# esp32md1.net
KiCad netlist of a schematic drawn in EAGLE
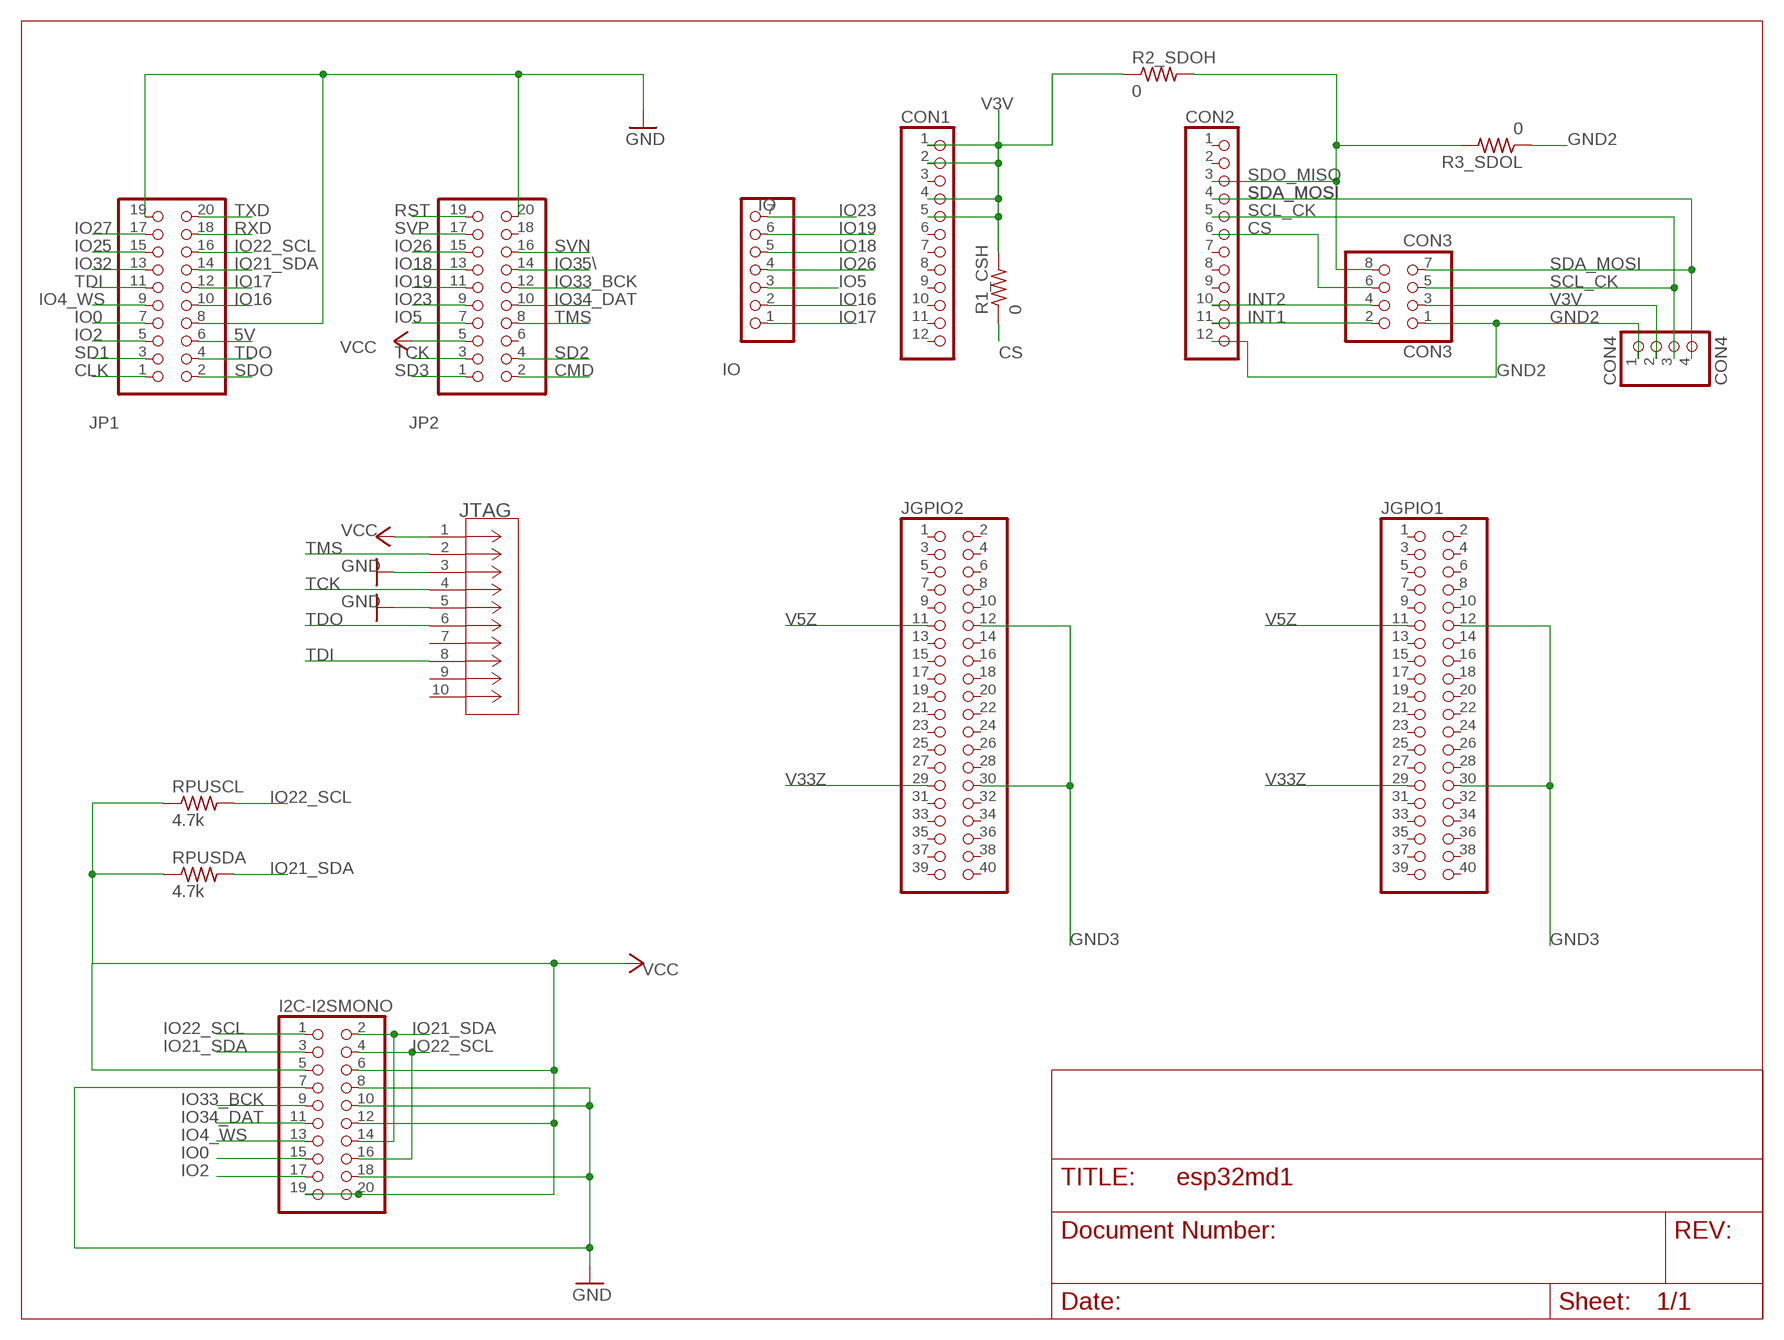
[diagram p0: schematic, sheet 1]

(export (version "E")
  (design (tool "Eeschema 10.0.6"))
  (components
    (comp (ref "CON1")
      (value "PINHD-1X12")
      (footprint "eagle-import:1X12")
      (libsource (lib "eagle-import") (part "PINHD-1X12"))
    )
    (comp (ref "CON2")
      (value "PINHD-1X12")
      (footprint "eagle-import:1X12")
      (libsource (lib "eagle-import") (part "PINHD-1X12"))
    )
    (comp (ref "CON3")
      (value "CON3")
      (footprint "eagle-import:2X04")
      (libsource (lib "eagle-import") (part "PINHD-2X4"))
    )
    (comp (ref "CON4")
      (value "CON4")
      (footprint "eagle-import:1X04")
      (libsource (lib "eagle-import") (part "PINHD-1X4"))
    )
    (comp (ref "I2C-I2SMONO")
      (value "PINHD-2X10")
      (footprint "eagle-import:2X10")
      (libsource (lib "eagle-import") (part "PINHD-2X10"))
    )
    (comp (ref "IO")
      (value "IO")
      (footprint "eagle-import:1X07")
      (libsource (lib "eagle-import") (part "PINHD-1X7"))
    )
    (comp (ref "JGPIO1")
      (value "PINHD-2X20")
      (footprint "eagle-import:2X20")
      (libsource (lib "eagle-import") (part "PINHD-2X20"))
    )
    (comp (ref "JGPIO2")
      (value "PINHD-2X20")
      (footprint "eagle-import:2X20")
      (libsource (lib "eagle-import") (part "PINHD-2X20"))
    )
    (comp (ref "JP1")
      (value "PINHD-2X10")
      (footprint "eagle-import:2X10")
      (libsource (lib "eagle-import") (part "PINHD-2X10"))
    )
    (comp (ref "JP2")
      (value "PINHD-2X10")
      (footprint "eagle-import:2X10")
      (libsource (lib "eagle-import") (part "PINHD-2X10"))
    )
    (comp (ref "JTAG")
      (value "M50-3600542CONN_M50-3600542_HRW-L")
      (footprint "eagle-import:CONN_M50-3600542_HRW-L")
      (fields
        (field (name "MANUFACTURER_PART_NUMBER") "M50-3600542")
        (field (name "COPYRIGHT") "Copyright (C) 2023 Ultra Librarian. All rights reserved.")
      )
      (libsource (lib "eagle-import") (part "M50-3600542CONN_M50-3600542_HRW-L"))
    )
    (comp (ref "R1_CSH")
      (value "0")
      (footprint "eagle-import:R0402")
      (libsource (lib "eagle-import") (part "R-US_R0402"))
    )
    (comp (ref "R2_SDOH")
      (value "0")
      (footprint "eagle-import:R0402")
      (libsource (lib "eagle-import") (part "R-US_R0402"))
    )
    (comp (ref "R3_SDOL")
      (value "0")
      (footprint "eagle-import:R0402")
      (libsource (lib "eagle-import") (part "R-US_R0402"))
    )
    (comp (ref "RPUSCL")
      (value "4.7k")
      (footprint "eagle-import:R0402")
      (libsource (lib "eagle-import") (part "R-US_R0402"))
    )
    (comp (ref "RPUSDA")
      (value "4.7k")
      (footprint "eagle-import:R0402")
      (libsource (lib "eagle-import") (part "R-US_R0402"))
    )
  )
  (nets
    (net (code "1") (name "/5V") (class "Default")
      (node (ref "JP1") (pin "6") (pinfunction "6_6") (pintype "passive"))
    )
    (net (code "2") (name "/CLK") (class "Default")
      (node (ref "JP1") (pin "1") (pinfunction "1_1") (pintype "passive"))
    )
    (net (code "3") (name "/CMD") (class "Default")
      (node (ref "JP2") (pin "2") (pinfunction "2_2") (pintype "passive"))
    )
    (net (code "4") (name "/CS") (class "Default")
      (node (ref "CON2") (pin "6") (pinfunction "6_6") (pintype "passive"))
      (node (ref "CON3") (pin "6") (pinfunction "6_6") (pintype "passive"))
      (node (ref "R1_CSH") (pin "1") (pinfunction "1_1") (pintype "passive"))
    )
    (net (code "5") (name "/GND2") (class "Default")
      (node (ref "CON2") (pin "12") (pinfunction "12_12") (pintype "passive"))
      (node (ref "CON3") (pin "1") (pinfunction "1_1") (pintype "passive"))
      (node (ref "CON4") (pin "1") (pinfunction "1_1") (pintype "passive"))
      (node (ref "R3_SDOL") (pin "1") (pinfunction "1_1") (pintype "passive"))
    )
    (net (code "6") (name "/GND3") (class "Default")
      (node (ref "JGPIO1") (pin "12") (pinfunction "12_12") (pintype "passive"))
      (node (ref "JGPIO1") (pin "30") (pinfunction "30_30") (pintype "passive"))
      (node (ref "JGPIO2") (pin "12") (pinfunction "12_12") (pintype "passive"))
      (node (ref "JGPIO2") (pin "30") (pinfunction "30_30") (pintype "passive"))
    )
    (net (code "7") (name "/INT1") (class "Default")
      (node (ref "CON2") (pin "11") (pinfunction "11_11") (pintype "passive"))
      (node (ref "CON3") (pin "2") (pinfunction "2_2") (pintype "passive"))
    )
    (net (code "8") (name "/INT2") (class "Default")
      (node (ref "CON2") (pin "10") (pinfunction "10_10") (pintype "passive"))
      (node (ref "CON3") (pin "4") (pinfunction "4_4") (pintype "passive"))
    )
    (net (code "9") (name "/IO0") (class "Default")
      (node (ref "I2C-I2SMONO") (pin "15") (pinfunction "15_15") (pintype "passive"))
      (node (ref "JP1") (pin "7") (pinfunction "7_7") (pintype "passive"))
    )
    (net (code "10") (name "/IO2") (class "Default")
      (node (ref "I2C-I2SMONO") (pin "17") (pinfunction "17_17") (pintype "passive"))
      (node (ref "JP1") (pin "5") (pinfunction "5_5") (pintype "passive"))
    )
    (net (code "11") (name "/IO4_WS") (class "Default")
      (node (ref "I2C-I2SMONO") (pin "13") (pinfunction "13_13") (pintype "passive"))
      (node (ref "JP1") (pin "9") (pinfunction "9_9") (pintype "passive"))
    )
    (net (code "12") (name "/IO5") (class "Default")
      (node (ref "IO") (pin "3") (pinfunction "3_3") (pintype "passive"))
      (node (ref "JP2") (pin "7") (pinfunction "7_7") (pintype "passive"))
    )
    (net (code "13") (name "/IO16") (class "Default")
      (node (ref "IO") (pin "2") (pinfunction "2_2") (pintype "passive"))
      (node (ref "JP1") (pin "10") (pinfunction "10_10") (pintype "passive"))
    )
    (net (code "14") (name "/IO17") (class "Default")
      (node (ref "IO") (pin "1") (pinfunction "1_1") (pintype "passive"))
      (node (ref "JP1") (pin "12") (pinfunction "12_12") (pintype "passive"))
    )
    (net (code "15") (name "/IO18") (class "Default")
      (node (ref "IO") (pin "5") (pinfunction "5_5") (pintype "passive"))
      (node (ref "JP2") (pin "13") (pinfunction "13_13") (pintype "passive"))
    )
    (net (code "16") (name "/IO19") (class "Default")
      (node (ref "IO") (pin "6") (pinfunction "6_6") (pintype "passive"))
      (node (ref "JP2") (pin "11") (pinfunction "11_11") (pintype "passive"))
    )
    (net (code "17") (name "/IO21_SDA") (class "Default")
      (node (ref "I2C-I2SMONO") (pin "14") (pinfunction "14_14") (pintype "passive"))
      (node (ref "I2C-I2SMONO") (pin "2") (pinfunction "2_2") (pintype "passive"))
      (node (ref "I2C-I2SMONO") (pin "3") (pinfunction "3_3") (pintype "passive"))
      (node (ref "JP1") (pin "14") (pinfunction "14_14") (pintype "passive"))
      (node (ref "RPUSDA") (pin "2") (pinfunction "2_2") (pintype "passive"))
    )
    (net (code "18") (name "/IO22_SCL") (class "Default")
      (node (ref "I2C-I2SMONO") (pin "1") (pinfunction "1_1") (pintype "passive"))
      (node (ref "I2C-I2SMONO") (pin "16") (pinfunction "16_16") (pintype "passive"))
      (node (ref "I2C-I2SMONO") (pin "4") (pinfunction "4_4") (pintype "passive"))
      (node (ref "JP1") (pin "16") (pinfunction "16_16") (pintype "passive"))
      (node (ref "RPUSCL") (pin "2") (pinfunction "2_2") (pintype "passive"))
    )
    (net (code "19") (name "/IO23") (class "Default")
      (node (ref "IO") (pin "7") (pinfunction "7_7") (pintype "passive"))
      (node (ref "JP2") (pin "9") (pinfunction "9_9") (pintype "passive"))
    )
    (net (code "20") (name "/IO25") (class "Default")
      (node (ref "JP1") (pin "15") (pinfunction "15_15") (pintype "passive"))
    )
    (net (code "21") (name "/IO26") (class "Default")
      (node (ref "IO") (pin "4") (pinfunction "4_4") (pintype "passive"))
      (node (ref "JP2") (pin "15") (pinfunction "15_15") (pintype "passive"))
    )
    (net (code "22") (name "/IO27") (class "Default")
      (node (ref "JP1") (pin "17") (pinfunction "17_17") (pintype "passive"))
    )
    (net (code "23") (name "/IO32") (class "Default")
      (node (ref "JP1") (pin "13") (pinfunction "13_13") (pintype "passive"))
    )
    (net (code "24") (name "/IO33_BCK") (class "Default")
      (node (ref "I2C-I2SMONO") (pin "9") (pinfunction "9_9") (pintype "passive"))
      (node (ref "JP2") (pin "12") (pinfunction "12_12") (pintype "passive"))
    )
    (net (code "25") (name "/IO34_DAT") (class "Default")
      (node (ref "I2C-I2SMONO") (pin "11") (pinfunction "11_11") (pintype "passive"))
      (node (ref "JP2") (pin "10") (pinfunction "10_10") (pintype "passive"))
    )
    (net (code "26") (name "/IO35\\") (class "Default")
      (node (ref "JP2") (pin "14") (pinfunction "14_14") (pintype "passive"))
    )
    (net (code "27") (name "/RST") (class "Default")
      (node (ref "JP2") (pin "19") (pinfunction "19_19") (pintype "passive"))
    )
    (net (code "28") (name "/RXD") (class "Default")
      (node (ref "JP1") (pin "18") (pinfunction "18_18") (pintype "passive"))
    )
    (net (code "29") (name "/SCL_CK") (class "Default")
      (node (ref "CON2") (pin "5") (pinfunction "5_5") (pintype "passive"))
      (node (ref "CON3") (pin "5") (pinfunction "5_5") (pintype "passive"))
      (node (ref "CON4") (pin "3") (pinfunction "3_3") (pintype "passive"))
    )
    (net (code "30") (name "/SD1") (class "Default")
      (node (ref "JP1") (pin "3") (pinfunction "3_3") (pintype "passive"))
    )
    (net (code "31") (name "/SD2") (class "Default")
      (node (ref "JP2") (pin "4") (pinfunction "4_4") (pintype "passive"))
    )
    (net (code "32") (name "/SD3") (class "Default")
      (node (ref "JP2") (pin "1") (pinfunction "1_1") (pintype "passive"))
    )
    (net (code "33") (name "/SDA_MOSI") (class "Default")
      (node (ref "CON2") (pin "4") (pinfunction "4_4") (pintype "passive"))
      (node (ref "CON3") (pin "7") (pinfunction "7_7") (pintype "passive"))
      (node (ref "CON4") (pin "4") (pinfunction "4_4") (pintype "passive"))
    )
    (net (code "34") (name "/SDO") (class "Default")
      (node (ref "JP1") (pin "2") (pinfunction "2_2") (pintype "passive"))
    )
    (net (code "35") (name "/SDO_MISO") (class "Default")
      (node (ref "CON2") (pin "3") (pinfunction "3_3") (pintype "passive"))
      (node (ref "CON3") (pin "8") (pinfunction "8_8") (pintype "passive"))
      (node (ref "R2_SDOH") (pin "2") (pinfunction "2_2") (pintype "passive"))
      (node (ref "R3_SDOL") (pin "2") (pinfunction "2_2") (pintype "passive"))
    )
    (net (code "36") (name "/SVN") (class "Default")
      (node (ref "JP2") (pin "16") (pinfunction "16_16") (pintype "passive"))
    )
    (net (code "37") (name "/SVP") (class "Default")
      (node (ref "JP2") (pin "17") (pinfunction "17_17") (pintype "passive"))
    )
    (net (code "38") (name "/TCK") (class "Default")
      (node (ref "JP2") (pin "3") (pinfunction "3_3") (pintype "passive"))
      (node (ref "JTAG") (pin "4") (pinfunction "4_4") (pintype "passive"))
    )
    (net (code "39") (name "/TDI") (class "Default")
      (node (ref "JP1") (pin "11") (pinfunction "11_11") (pintype "passive"))
      (node (ref "JTAG") (pin "8") (pinfunction "8_8") (pintype "passive"))
    )
    (net (code "40") (name "/TDO") (class "Default")
      (node (ref "JP1") (pin "4") (pinfunction "4_4") (pintype "passive"))
      (node (ref "JTAG") (pin "6") (pinfunction "6_6") (pintype "passive"))
    )
    (net (code "41") (name "/TMS") (class "Default")
      (node (ref "JP2") (pin "8") (pinfunction "8_8") (pintype "passive"))
      (node (ref "JTAG") (pin "2") (pinfunction "2_2") (pintype "passive"))
    )
    (net (code "42") (name "/TXD") (class "Default")
      (node (ref "JP1") (pin "20") (pinfunction "20_20") (pintype "passive"))
    )
    (net (code "43") (name "/V3V") (class "Default")
      (node (ref "CON1") (pin "1") (pinfunction "1_1") (pintype "passive"))
      (node (ref "CON1") (pin "2") (pinfunction "2_2") (pintype "passive"))
      (node (ref "CON1") (pin "4") (pinfunction "4_4") (pintype "passive"))
      (node (ref "CON1") (pin "5") (pinfunction "5_5") (pintype "passive"))
      (node (ref "CON3") (pin "3") (pinfunction "3_3") (pintype "passive"))
      (node (ref "CON4") (pin "2") (pinfunction "2_2") (pintype "passive"))
      (node (ref "R1_CSH") (pin "2") (pinfunction "2_2") (pintype "passive"))
      (node (ref "R2_SDOH") (pin "1") (pinfunction "1_1") (pintype "passive"))
    )
    (net (code "44") (name "/V5Z") (class "Default")
      (node (ref "JGPIO1") (pin "11") (pinfunction "11_11") (pintype "passive"))
      (node (ref "JGPIO2") (pin "11") (pinfunction "11_11") (pintype "passive"))
    )
    (net (code "45") (name "/V33Z") (class "Default")
      (node (ref "JGPIO1") (pin "29") (pinfunction "29_29") (pintype "passive"))
      (node (ref "JGPIO2") (pin "29") (pinfunction "29_29") (pintype "passive"))
    )
    (net (code "46") (name "GND") (class "Default")
      (node (ref "I2C-I2SMONO") (pin "10") (pinfunction "10_10") (pintype "passive"))
      (node (ref "I2C-I2SMONO") (pin "18") (pinfunction "18_18") (pintype "passive"))
      (node (ref "I2C-I2SMONO") (pin "7") (pinfunction "7_7") (pintype "passive"))
      (node (ref "I2C-I2SMONO") (pin "8") (pinfunction "8_8") (pintype "passive"))
      (node (ref "JP1") (pin "19") (pinfunction "19_19") (pintype "passive"))
      (node (ref "JP1") (pin "8") (pinfunction "8_8") (pintype "passive"))
      (node (ref "JP2") (pin "20") (pinfunction "20_20") (pintype "passive"))
      (node (ref "JTAG") (pin "3") (pinfunction "3_3") (pintype "passive"))
      (node (ref "JTAG") (pin "5") (pinfunction "5_5") (pintype "passive"))
    )
    (net (code "47") (name "VCC") (class "Default")
      (node (ref "I2C-I2SMONO") (pin "12") (pinfunction "12_12") (pintype "passive"))
      (node (ref "I2C-I2SMONO") (pin "19") (pinfunction "19_19") (pintype "passive"))
      (node (ref "I2C-I2SMONO") (pin "20") (pinfunction "20_20") (pintype "passive"))
      (node (ref "I2C-I2SMONO") (pin "5") (pinfunction "5_5") (pintype "passive"))
      (node (ref "I2C-I2SMONO") (pin "6") (pinfunction "6_6") (pintype "passive"))
      (node (ref "JP2") (pin "5") (pinfunction "5_5") (pintype "passive"))
      (node (ref "JTAG") (pin "1") (pinfunction "1_1") (pintype "passive"))
      (node (ref "RPUSCL") (pin "1") (pinfunction "1_1") (pintype "passive"))
      (node (ref "RPUSDA") (pin "1") (pinfunction "1_1") (pintype "passive"))
    )
    (net (code "48") (name "unconnected-(CON1-Pad3)") (class "Default")
      (node (ref "CON1") (pin "3") (pinfunction "3_3") (pintype "passive"))
    )
    (net (code "49") (name "unconnected-(CON1-Pad6)") (class "Default")
      (node (ref "CON1") (pin "6") (pinfunction "6_6") (pintype "passive"))
    )
    (net (code "50") (name "unconnected-(CON1-Pad7)") (class "Default")
      (node (ref "CON1") (pin "7") (pinfunction "7_7") (pintype "passive"))
    )
    (net (code "51") (name "unconnected-(CON1-Pad8)") (class "Default")
      (node (ref "CON1") (pin "8") (pinfunction "8_8") (pintype "passive"))
    )
    (net (code "52") (name "unconnected-(CON1-Pad9)") (class "Default")
      (node (ref "CON1") (pin "9") (pinfunction "9_9") (pintype "passive"))
    )
    (net (code "53") (name "unconnected-(CON1-Pad10)") (class "Default")
      (node (ref "CON1") (pin "10") (pinfunction "10_10") (pintype "passive"))
    )
    (net (code "54") (name "unconnected-(CON1-Pad11)") (class "Default")
      (node (ref "CON1") (pin "11") (pinfunction "11_11") (pintype "passive"))
    )
    (net (code "55") (name "unconnected-(CON1-Pad12)") (class "Default")
      (node (ref "CON1") (pin "12") (pinfunction "12_12") (pintype "passive"))
    )
    (net (code "56") (name "unconnected-(CON2-Pad1)") (class "Default")
      (node (ref "CON2") (pin "1") (pinfunction "1_1") (pintype "passive"))
    )
    (net (code "57") (name "unconnected-(CON2-Pad2)") (class "Default")
      (node (ref "CON2") (pin "2") (pinfunction "2_2") (pintype "passive"))
    )
    (net (code "58") (name "unconnected-(CON2-Pad7)") (class "Default")
      (node (ref "CON2") (pin "7") (pinfunction "7_7") (pintype "passive"))
    )
    (net (code "59") (name "unconnected-(CON2-Pad8)") (class "Default")
      (node (ref "CON2") (pin "8") (pinfunction "8_8") (pintype "passive"))
    )
    (net (code "60") (name "unconnected-(CON2-Pad9)") (class "Default")
      (node (ref "CON2") (pin "9") (pinfunction "9_9") (pintype "passive"))
    )
    (net (code "61") (name "unconnected-(JGPIO1-Pad1)") (class "Default")
      (node (ref "JGPIO1") (pin "1") (pinfunction "1_1") (pintype "passive"))
    )
    (net (code "62") (name "unconnected-(JGPIO1-Pad2)") (class "Default")
      (node (ref "JGPIO1") (pin "2") (pinfunction "2_2") (pintype "passive"))
    )
    (net (code "63") (name "unconnected-(JGPIO1-Pad3)") (class "Default")
      (node (ref "JGPIO1") (pin "3") (pinfunction "3_3") (pintype "passive"))
    )
    (net (code "64") (name "unconnected-(JGPIO1-Pad4)") (class "Default")
      (node (ref "JGPIO1") (pin "4") (pinfunction "4_4") (pintype "passive"))
    )
    (net (code "65") (name "unconnected-(JGPIO1-Pad5)") (class "Default")
      (node (ref "JGPIO1") (pin "5") (pinfunction "5_5") (pintype "passive"))
    )
    (net (code "66") (name "unconnected-(JGPIO1-Pad6)") (class "Default")
      (node (ref "JGPIO1") (pin "6") (pinfunction "6_6") (pintype "passive"))
    )
    (net (code "67") (name "unconnected-(JGPIO1-Pad7)") (class "Default")
      (node (ref "JGPIO1") (pin "7") (pinfunction "7_7") (pintype "passive"))
    )
    (net (code "68") (name "unconnected-(JGPIO1-Pad8)") (class "Default")
      (node (ref "JGPIO1") (pin "8") (pinfunction "8_8") (pintype "passive"))
    )
    (net (code "69") (name "unconnected-(JGPIO1-Pad9)") (class "Default")
      (node (ref "JGPIO1") (pin "9") (pinfunction "9_9") (pintype "passive"))
    )
    (net (code "70") (name "unconnected-(JGPIO1-Pad10)") (class "Default")
      (node (ref "JGPIO1") (pin "10") (pinfunction "10_10") (pintype "passive"))
    )
    (net (code "71") (name "unconnected-(JGPIO1-Pad13)") (class "Default")
      (node (ref "JGPIO1") (pin "13") (pinfunction "13_13") (pintype "passive"))
    )
    (net (code "72") (name "unconnected-(JGPIO1-Pad14)") (class "Default")
      (node (ref "JGPIO1") (pin "14") (pinfunction "14_14") (pintype "passive"))
    )
    (net (code "73") (name "unconnected-(JGPIO1-Pad15)") (class "Default")
      (node (ref "JGPIO1") (pin "15") (pinfunction "15_15") (pintype "passive"))
    )
    (net (code "74") (name "unconnected-(JGPIO1-Pad16)") (class "Default")
      (node (ref "JGPIO1") (pin "16") (pinfunction "16_16") (pintype "passive"))
    )
    (net (code "75") (name "unconnected-(JGPIO1-Pad17)") (class "Default")
      (node (ref "JGPIO1") (pin "17") (pinfunction "17_17") (pintype "passive"))
    )
    (net (code "76") (name "unconnected-(JGPIO1-Pad18)") (class "Default")
      (node (ref "JGPIO1") (pin "18") (pinfunction "18_18") (pintype "passive"))
    )
    (net (code "77") (name "unconnected-(JGPIO1-Pad19)") (class "Default")
      (node (ref "JGPIO1") (pin "19") (pinfunction "19_19") (pintype "passive"))
    )
    (net (code "78") (name "unconnected-(JGPIO1-Pad20)") (class "Default")
      (node (ref "JGPIO1") (pin "20") (pinfunction "20_20") (pintype "passive"))
    )
    (net (code "79") (name "unconnected-(JGPIO1-Pad21)") (class "Default")
      (node (ref "JGPIO1") (pin "21") (pinfunction "21_21") (pintype "passive"))
    )
    (net (code "80") (name "unconnected-(JGPIO1-Pad22)") (class "Default")
      (node (ref "JGPIO1") (pin "22") (pinfunction "22_22") (pintype "passive"))
    )
    (net (code "81") (name "unconnected-(JGPIO1-Pad23)") (class "Default")
      (node (ref "JGPIO1") (pin "23") (pinfunction "23_23") (pintype "passive"))
    )
    (net (code "82") (name "unconnected-(JGPIO1-Pad24)") (class "Default")
      (node (ref "JGPIO1") (pin "24") (pinfunction "24_24") (pintype "passive"))
    )
    (net (code "83") (name "unconnected-(JGPIO1-Pad25)") (class "Default")
      (node (ref "JGPIO1") (pin "25") (pinfunction "25_25") (pintype "passive"))
    )
    (net (code "84") (name "unconnected-(JGPIO1-Pad26)") (class "Default")
      (node (ref "JGPIO1") (pin "26") (pinfunction "26_26") (pintype "passive"))
    )
    (net (code "85") (name "unconnected-(JGPIO1-Pad27)") (class "Default")
      (node (ref "JGPIO1") (pin "27") (pinfunction "27_27") (pintype "passive"))
    )
    (net (code "86") (name "unconnected-(JGPIO1-Pad28)") (class "Default")
      (node (ref "JGPIO1") (pin "28") (pinfunction "28_28") (pintype "passive"))
    )
    (net (code "87") (name "unconnected-(JGPIO1-Pad31)") (class "Default")
      (node (ref "JGPIO1") (pin "31") (pinfunction "31_31") (pintype "passive"))
    )
    (net (code "88") (name "unconnected-(JGPIO1-Pad32)") (class "Default")
      (node (ref "JGPIO1") (pin "32") (pinfunction "32_32") (pintype "passive"))
    )
    (net (code "89") (name "unconnected-(JGPIO1-Pad33)") (class "Default")
      (node (ref "JGPIO1") (pin "33") (pinfunction "33_33") (pintype "passive"))
    )
    (net (code "90") (name "unconnected-(JGPIO1-Pad34)") (class "Default")
      (node (ref "JGPIO1") (pin "34") (pinfunction "34_34") (pintype "passive"))
    )
    (net (code "91") (name "unconnected-(JGPIO1-Pad35)") (class "Default")
      (node (ref "JGPIO1") (pin "35") (pinfunction "35_35") (pintype "passive"))
    )
    (net (code "92") (name "unconnected-(JGPIO1-Pad36)") (class "Default")
      (node (ref "JGPIO1") (pin "36") (pinfunction "36_36") (pintype "passive"))
    )
    (net (code "93") (name "unconnected-(JGPIO1-Pad37)") (class "Default")
      (node (ref "JGPIO1") (pin "37") (pinfunction "37_37") (pintype "passive"))
    )
    (net (code "94") (name "unconnected-(JGPIO1-Pad38)") (class "Default")
      (node (ref "JGPIO1") (pin "38") (pinfunction "38_38") (pintype "passive"))
    )
    (net (code "95") (name "unconnected-(JGPIO1-Pad39)") (class "Default")
      (node (ref "JGPIO1") (pin "39") (pinfunction "39_39") (pintype "passive"))
    )
    (net (code "96") (name "unconnected-(JGPIO1-Pad40)") (class "Default")
      (node (ref "JGPIO1") (pin "40") (pinfunction "40_40") (pintype "passive"))
    )
    (net (code "97") (name "unconnected-(JGPIO2-Pad1)") (class "Default")
      (node (ref "JGPIO2") (pin "1") (pinfunction "1_1") (pintype "passive"))
    )
    (net (code "98") (name "unconnected-(JGPIO2-Pad2)") (class "Default")
      (node (ref "JGPIO2") (pin "2") (pinfunction "2_2") (pintype "passive"))
    )
    (net (code "99") (name "unconnected-(JGPIO2-Pad3)") (class "Default")
      (node (ref "JGPIO2") (pin "3") (pinfunction "3_3") (pintype "passive"))
    )
    (net (code "100") (name "unconnected-(JGPIO2-Pad4)") (class "Default")
      (node (ref "JGPIO2") (pin "4") (pinfunction "4_4") (pintype "passive"))
    )
    (net (code "101") (name "unconnected-(JGPIO2-Pad5)") (class "Default")
      (node (ref "JGPIO2") (pin "5") (pinfunction "5_5") (pintype "passive"))
    )
    (net (code "102") (name "unconnected-(JGPIO2-Pad6)") (class "Default")
      (node (ref "JGPIO2") (pin "6") (pinfunction "6_6") (pintype "passive"))
    )
    (net (code "103") (name "unconnected-(JGPIO2-Pad7)") (class "Default")
      (node (ref "JGPIO2") (pin "7") (pinfunction "7_7") (pintype "passive"))
    )
    (net (code "104") (name "unconnected-(JGPIO2-Pad8)") (class "Default")
      (node (ref "JGPIO2") (pin "8") (pinfunction "8_8") (pintype "passive"))
    )
    (net (code "105") (name "unconnected-(JGPIO2-Pad9)") (class "Default")
      (node (ref "JGPIO2") (pin "9") (pinfunction "9_9") (pintype "passive"))
    )
    (net (code "106") (name "unconnected-(JGPIO2-Pad10)") (class "Default")
      (node (ref "JGPIO2") (pin "10") (pinfunction "10_10") (pintype "passive"))
    )
    (net (code "107") (name "unconnected-(JGPIO2-Pad13)") (class "Default")
      (node (ref "JGPIO2") (pin "13") (pinfunction "13_13") (pintype "passive"))
    )
    (net (code "108") (name "unconnected-(JGPIO2-Pad14)") (class "Default")
      (node (ref "JGPIO2") (pin "14") (pinfunction "14_14") (pintype "passive"))
    )
    (net (code "109") (name "unconnected-(JGPIO2-Pad15)") (class "Default")
      (node (ref "JGPIO2") (pin "15") (pinfunction "15_15") (pintype "passive"))
    )
    (net (code "110") (name "unconnected-(JGPIO2-Pad16)") (class "Default")
      (node (ref "JGPIO2") (pin "16") (pinfunction "16_16") (pintype "passive"))
    )
    (net (code "111") (name "unconnected-(JGPIO2-Pad17)") (class "Default")
      (node (ref "JGPIO2") (pin "17") (pinfunction "17_17") (pintype "passive"))
    )
    (net (code "112") (name "unconnected-(JGPIO2-Pad18)") (class "Default")
      (node (ref "JGPIO2") (pin "18") (pinfunction "18_18") (pintype "passive"))
    )
    (net (code "113") (name "unconnected-(JGPIO2-Pad19)") (class "Default")
      (node (ref "JGPIO2") (pin "19") (pinfunction "19_19") (pintype "passive"))
    )
    (net (code "114") (name "unconnected-(JGPIO2-Pad20)") (class "Default")
      (node (ref "JGPIO2") (pin "20") (pinfunction "20_20") (pintype "passive"))
    )
    (net (code "115") (name "unconnected-(JGPIO2-Pad21)") (class "Default")
      (node (ref "JGPIO2") (pin "21") (pinfunction "21_21") (pintype "passive"))
    )
    (net (code "116") (name "unconnected-(JGPIO2-Pad22)") (class "Default")
      (node (ref "JGPIO2") (pin "22") (pinfunction "22_22") (pintype "passive"))
    )
    (net (code "117") (name "unconnected-(JGPIO2-Pad23)") (class "Default")
      (node (ref "JGPIO2") (pin "23") (pinfunction "23_23") (pintype "passive"))
    )
    (net (code "118") (name "unconnected-(JGPIO2-Pad24)") (class "Default")
      (node (ref "JGPIO2") (pin "24") (pinfunction "24_24") (pintype "passive"))
    )
    (net (code "119") (name "unconnected-(JGPIO2-Pad25)") (class "Default")
      (node (ref "JGPIO2") (pin "25") (pinfunction "25_25") (pintype "passive"))
    )
    (net (code "120") (name "unconnected-(JGPIO2-Pad26)") (class "Default")
      (node (ref "JGPIO2") (pin "26") (pinfunction "26_26") (pintype "passive"))
    )
    (net (code "121") (name "unconnected-(JGPIO2-Pad27)") (class "Default")
      (node (ref "JGPIO2") (pin "27") (pinfunction "27_27") (pintype "passive"))
    )
    (net (code "122") (name "unconnected-(JGPIO2-Pad28)") (class "Default")
      (node (ref "JGPIO2") (pin "28") (pinfunction "28_28") (pintype "passive"))
    )
    (net (code "123") (name "unconnected-(JGPIO2-Pad31)") (class "Default")
      (node (ref "JGPIO2") (pin "31") (pinfunction "31_31") (pintype "passive"))
    )
    (net (code "124") (name "unconnected-(JGPIO2-Pad32)") (class "Default")
      (node (ref "JGPIO2") (pin "32") (pinfunction "32_32") (pintype "passive"))
    )
    (net (code "125") (name "unconnected-(JGPIO2-Pad33)") (class "Default")
      (node (ref "JGPIO2") (pin "33") (pinfunction "33_33") (pintype "passive"))
    )
    (net (code "126") (name "unconnected-(JGPIO2-Pad34)") (class "Default")
      (node (ref "JGPIO2") (pin "34") (pinfunction "34_34") (pintype "passive"))
    )
    (net (code "127") (name "unconnected-(JGPIO2-Pad35)") (class "Default")
      (node (ref "JGPIO2") (pin "35") (pinfunction "35_35") (pintype "passive"))
    )
    (net (code "128") (name "unconnected-(JGPIO2-Pad36)") (class "Default")
      (node (ref "JGPIO2") (pin "36") (pinfunction "36_36") (pintype "passive"))
    )
    (net (code "129") (name "unconnected-(JGPIO2-Pad37)") (class "Default")
      (node (ref "JGPIO2") (pin "37") (pinfunction "37_37") (pintype "passive"))
    )
    (net (code "130") (name "unconnected-(JGPIO2-Pad38)") (class "Default")
      (node (ref "JGPIO2") (pin "38") (pinfunction "38_38") (pintype "passive"))
    )
    (net (code "131") (name "unconnected-(JGPIO2-Pad39)") (class "Default")
      (node (ref "JGPIO2") (pin "39") (pinfunction "39_39") (pintype "passive"))
    )
    (net (code "132") (name "unconnected-(JGPIO2-Pad40)") (class "Default")
      (node (ref "JGPIO2") (pin "40") (pinfunction "40_40") (pintype "passive"))
    )
    (net (code "133") (name "unconnected-(JP2-Pad6)") (class "Default")
      (node (ref "JP2") (pin "6") (pinfunction "6_6") (pintype "passive"))
    )
    (net (code "134") (name "unconnected-(JP2-Pad18)") (class "Default")
      (node (ref "JP2") (pin "18") (pinfunction "18_18") (pintype "passive"))
    )
    (net (code "135") (name "unconnected-(JTAG-Pad7)") (class "Default")
      (node (ref "JTAG") (pin "7") (pinfunction "7_7") (pintype "passive"))
    )
    (net (code "136") (name "unconnected-(JTAG-Pad9)") (class "Default")
      (node (ref "JTAG") (pin "9") (pinfunction "9_9") (pintype "passive"))
    )
    (net (code "137") (name "unconnected-(JTAG-Pad10)") (class "Default")
      (node (ref "JTAG") (pin "10") (pinfunction "10_10") (pintype "passive"))
    )
  )
)
